# Screen.net
KiCad netlist of a schematic drawn in Altium Designer
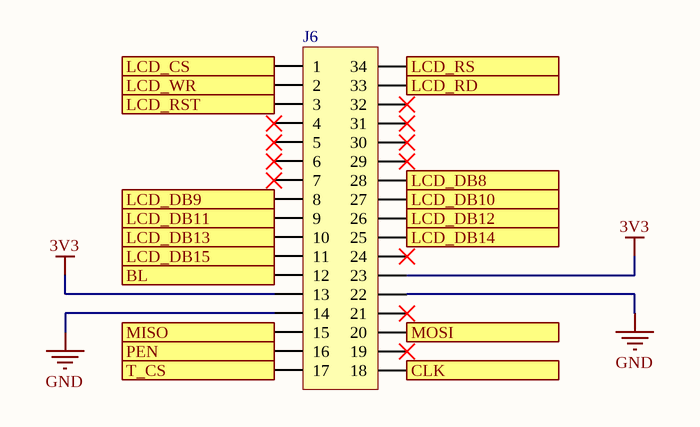
[diagram p0: Screen.SchDoc]

(export (version "E")
  (design (tool "Eeschema 10.0.6"))
  (components
    (comp (ref "J6")
      (value "JP17x2")
      (footprint "JP17-C2T")
      (description "WR-PHD 2.54 mm Dual Socket Header")
      (fields
        (field (name "MANUFACTURER") "Würth Elektronik eiSos GmbH")
        (field (name "PARTNO") "61303421821")
        (field (name "CREATED BY") "Karrer Zheng")
      )
      (libsource (lib "My Library") (part "JP17x2"))
    )
  )
  (nets
    (net (code "1") (name "/BL") (class "Default")
      (node (ref "J6") (pin "12") (pinfunction "12_12") (pintype "passive"))
    )
    (net (code "2") (name "/CLK") (class "Default")
      (node (ref "J6") (pin "18") (pinfunction "18_18") (pintype "passive"))
    )
    (net (code "3") (name "/LCD_CS") (class "Default")
      (node (ref "J6") (pin "1") (pinfunction "1_1") (pintype "passive"))
    )
    (net (code "4") (name "/LCD_DB8") (class "Default")
      (node (ref "J6") (pin "28") (pinfunction "28_28") (pintype "passive"))
    )
    (net (code "5") (name "/LCD_DB9") (class "Default")
      (node (ref "J6") (pin "8") (pinfunction "8_8") (pintype "passive"))
    )
    (net (code "6") (name "/LCD_DB10") (class "Default")
      (node (ref "J6") (pin "27") (pinfunction "27_27") (pintype "passive"))
    )
    (net (code "7") (name "/LCD_DB11") (class "Default")
      (node (ref "J6") (pin "9") (pinfunction "9_9") (pintype "passive"))
    )
    (net (code "8") (name "/LCD_DB12") (class "Default")
      (node (ref "J6") (pin "26") (pinfunction "26_26") (pintype "passive"))
    )
    (net (code "9") (name "/LCD_DB13") (class "Default")
      (node (ref "J6") (pin "10") (pinfunction "10_10") (pintype "passive"))
    )
    (net (code "10") (name "/LCD_DB14") (class "Default")
      (node (ref "J6") (pin "25") (pinfunction "25_25") (pintype "passive"))
    )
    (net (code "11") (name "/LCD_DB15") (class "Default")
      (node (ref "J6") (pin "11") (pinfunction "11_11") (pintype "passive"))
    )
    (net (code "12") (name "/LCD_RD") (class "Default")
      (node (ref "J6") (pin "33") (pinfunction "33_33") (pintype "passive"))
    )
    (net (code "13") (name "/LCD_RS") (class "Default")
      (node (ref "J6") (pin "34") (pinfunction "34_34") (pintype "passive"))
    )
    (net (code "14") (name "/LCD_RST") (class "Default")
      (node (ref "J6") (pin "3") (pinfunction "3_3") (pintype "passive"))
    )
    (net (code "15") (name "/LCD_WR") (class "Default")
      (node (ref "J6") (pin "2") (pinfunction "2_2") (pintype "passive"))
    )
    (net (code "16") (name "/MISO") (class "Default")
      (node (ref "J6") (pin "15") (pinfunction "15_15") (pintype "passive"))
    )
    (net (code "17") (name "/MOSI") (class "Default")
      (node (ref "J6") (pin "20") (pinfunction "20_20") (pintype "passive"))
    )
    (net (code "18") (name "/PEN") (class "Default")
      (node (ref "J6") (pin "16") (pinfunction "16_16") (pintype "passive"))
    )
    (net (code "19") (name "/T_CS") (class "Default")
      (node (ref "J6") (pin "17") (pinfunction "17_17") (pintype "passive"))
    )
    (net (code "20") (name "3V3") (class "Default")
      (node (ref "J6") (pin "13") (pinfunction "13_13") (pintype "passive"))
      (node (ref "J6") (pin "23") (pinfunction "23_23") (pintype "passive"))
    )
    (net (code "21") (name "GND") (class "Default")
      (node (ref "J6") (pin "14") (pinfunction "14_14") (pintype "passive"))
      (node (ref "J6") (pin "22") (pinfunction "22_22") (pintype "passive"))
    )
    (net (code "22") (name "unconnected-(J6-Pad4)") (class "Default")
      (node (ref "J6") (pin "4") (pinfunction "4_4") (pintype "passive+no_connect"))
    )
    (net (code "23") (name "unconnected-(J6-Pad5)") (class "Default")
      (node (ref "J6") (pin "5") (pinfunction "5_5") (pintype "passive+no_connect"))
    )
    (net (code "24") (name "unconnected-(J6-Pad6)") (class "Default")
      (node (ref "J6") (pin "6") (pinfunction "6_6") (pintype "passive+no_connect"))
    )
    (net (code "25") (name "unconnected-(J6-Pad7)") (class "Default")
      (node (ref "J6") (pin "7") (pinfunction "7_7") (pintype "passive+no_connect"))
    )
    (net (code "26") (name "unconnected-(J6-Pad19)") (class "Default")
      (node (ref "J6") (pin "19") (pinfunction "19_19") (pintype "passive+no_connect"))
    )
    (net (code "27") (name "unconnected-(J6-Pad21)") (class "Default")
      (node (ref "J6") (pin "21") (pinfunction "21_21") (pintype "passive+no_connect"))
    )
    (net (code "28") (name "unconnected-(J6-Pad24)") (class "Default")
      (node (ref "J6") (pin "24") (pinfunction "24_24") (pintype "passive+no_connect"))
    )
    (net (code "29") (name "unconnected-(J6-Pad29)") (class "Default")
      (node (ref "J6") (pin "29") (pinfunction "29_29") (pintype "passive+no_connect"))
    )
    (net (code "30") (name "unconnected-(J6-Pad30)") (class "Default")
      (node (ref "J6") (pin "30") (pinfunction "30_30") (pintype "passive+no_connect"))
    )
    (net (code "31") (name "unconnected-(J6-Pad31)") (class "Default")
      (node (ref "J6") (pin "31") (pinfunction "31_31") (pintype "passive+no_connect"))
    )
    (net (code "32") (name "unconnected-(J6-Pad32)") (class "Default")
      (node (ref "J6") (pin "32") (pinfunction "32_32") (pintype "passive+no_connect"))
    )
  )
)
